# Final_LDO.net
KiCad netlist of a schematic drawn in Altium Designer
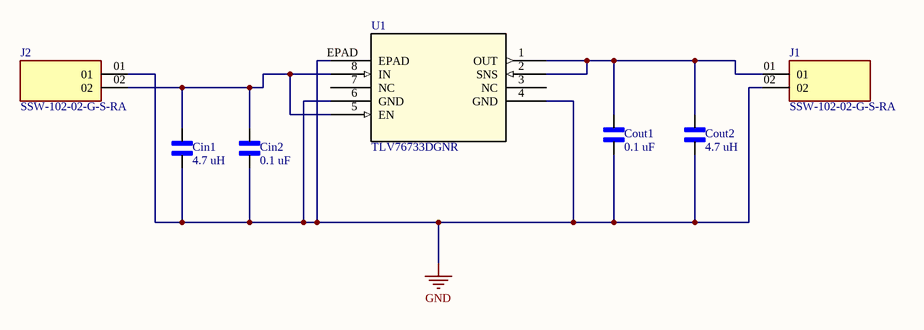
[diagram p0: Final_LDO.SchDoc]

(export (version "E")
  (design (tool "Eeschema 10.0.6"))
  (components
    (comp (ref "Cin1")
      (value "4.7 uH")
      (footprint "CAPC2012X140N")
      (description "SMD capacitor X7R(EIA) with capacitance 10uF Tol.10%. Rated voltage 10Vdc 125C")
      (fields (field (name "MP") "GRM21BR71A106KA73L") (field (name "MF") "Murata Electronics"))
      (libsource (lib "Kaitlynnly") (part "GRM21BR71A106KA73L"))
    )
    (comp (ref "Cin2")
      (value "0.1 uF")
      (footprint "CAPC1608X95")
      (description "0.1 ÂµF Â±10% 16V Ceramic Capacitor X7R 0603 (1608 Metric)")
      (fields (field (name "MP") "C1608X7R1C104KT") (field (name "MF") "TDK"))
      (libsource (lib "Kaitlynnly") (part "C1608X7R1C104KT"))
    )
    (comp (ref "Cout1")
      (value "0.1 uF")
      (footprint "CAPC1608X95")
      (description "0.1 ÂµF Â±10% 16V Ceramic Capacitor X7R 0603 (1608 Metric)")
      (fields (field (name "MP") "C1608X7R1C104KT") (field (name "MF") "TDK"))
      (libsource (lib "Kaitlynnly") (part "C1608X7R1C104KT"))
    )
    (comp (ref "Cout2")
      (value "4.7 uH")
      (footprint "CAPC2012X140N")
      (description "SMD capacitor X7R(EIA) with capacitance 10uF Tol.10%. Rated voltage 10Vdc 125C")
      (fields (field (name "MP") "GRM21BR71A106KA73L") (field (name "MF") "Murata Electronics"))
      (libsource (lib "Kaitlynnly") (part "GRM21BR71A106KA73L"))
    )
    (comp (ref "J1")
      (value "SSW-102-02-G-S-RA")
      (footprint "SAMTEC_SSW-102-02-G-S-RA")
      (fields (field (name "MF") "Samtec"))
      (libsource (lib "") (part "SSW-102-02-G-S-RA_1"))
    )
    (comp (ref "J2")
      (value "SSW-102-02-G-S-RA")
      (footprint "SAMTEC_SSW-102-02-G-S-RA")
      (fields (field (name "MF") "Samtec"))
      (libsource (lib "SSW-102-02-G-S-RA") (part "SSW-102-02-G-S-RA"))
    )
    (comp (ref "U1")
      (value "TLV76733DGNR")
      (footprint "VSSOP8_DGN_TEX")
      (fields (field (name "COPYRIGHT") "Copyright (C) 2025 Ultra Librarian. All rights reserved."))
      (libsource (lib "TLV76733DGNR") (part "TLV76733DGNR"))
    )
  )
  (nets
    (net (code "1") (name "GND") (class "Default")
      (node (ref "Cin1") (pin "1") (pinfunction "1_1") (pintype "passive"))
      (node (ref "Cin2") (pin "2") (pinfunction "2_2") (pintype "passive"))
      (node (ref "Cout1") (pin "2") (pinfunction "2_2") (pintype "passive"))
      (node (ref "Cout2") (pin "1") (pinfunction "1_1") (pintype "passive"))
      (node (ref "J1") (pin "02") (pinfunction "02_02") (pintype "passive"))
      (node (ref "J2") (pin "01") (pinfunction "01_01") (pintype "passive"))
      (node (ref "U1") (pin "4") (pinfunction "GND_4") (pintype "power_in"))
      (node (ref "U1") (pin "6") (pinfunction "GND_6") (pintype "power_in"))
      (node (ref "U1") (pin "EPAD") (pinfunction "EPAD_EPAD") (pintype "power_in"))
    )
    (net (code "2") (name "Net-(U1-EN)") (class "Default")
      (node (ref "Cin1") (pin "2") (pinfunction "2_2") (pintype "passive"))
      (node (ref "Cin2") (pin "1") (pinfunction "1_1") (pintype "passive"))
      (node (ref "J2") (pin "02") (pinfunction "02_02") (pintype "passive"))
      (node (ref "U1") (pin "5") (pinfunction "EN_5") (pintype "input"))
      (node (ref "U1") (pin "8") (pinfunction "IN_8") (pintype "input"))
    )
    (net (code "3") (name "Net-(U1-OUT)") (class "Default")
      (node (ref "Cout1") (pin "1") (pinfunction "1_1") (pintype "passive"))
      (node (ref "Cout2") (pin "2") (pinfunction "2_2") (pintype "passive"))
      (node (ref "J1") (pin "01") (pinfunction "01_01") (pintype "passive"))
      (node (ref "U1") (pin "1") (pinfunction "OUT_1") (pintype "output"))
      (node (ref "U1") (pin "2") (pinfunction "SNS_2") (pintype "input"))
    )
    (net (code "4") (name "unconnected-(U1-NC-Pad3)") (class "Default")
      (node (ref "U1") (pin "3") (pinfunction "NC_3") (pintype "passive"))
    )
    (net (code "5") (name "unconnected-(U1-NC-Pad7)") (class "Default")
      (node (ref "U1") (pin "7") (pinfunction "NC_7") (pintype "passive"))
    )
  )
)
